# all.net
KiCad netlist of a schematic drawn in EAGLE
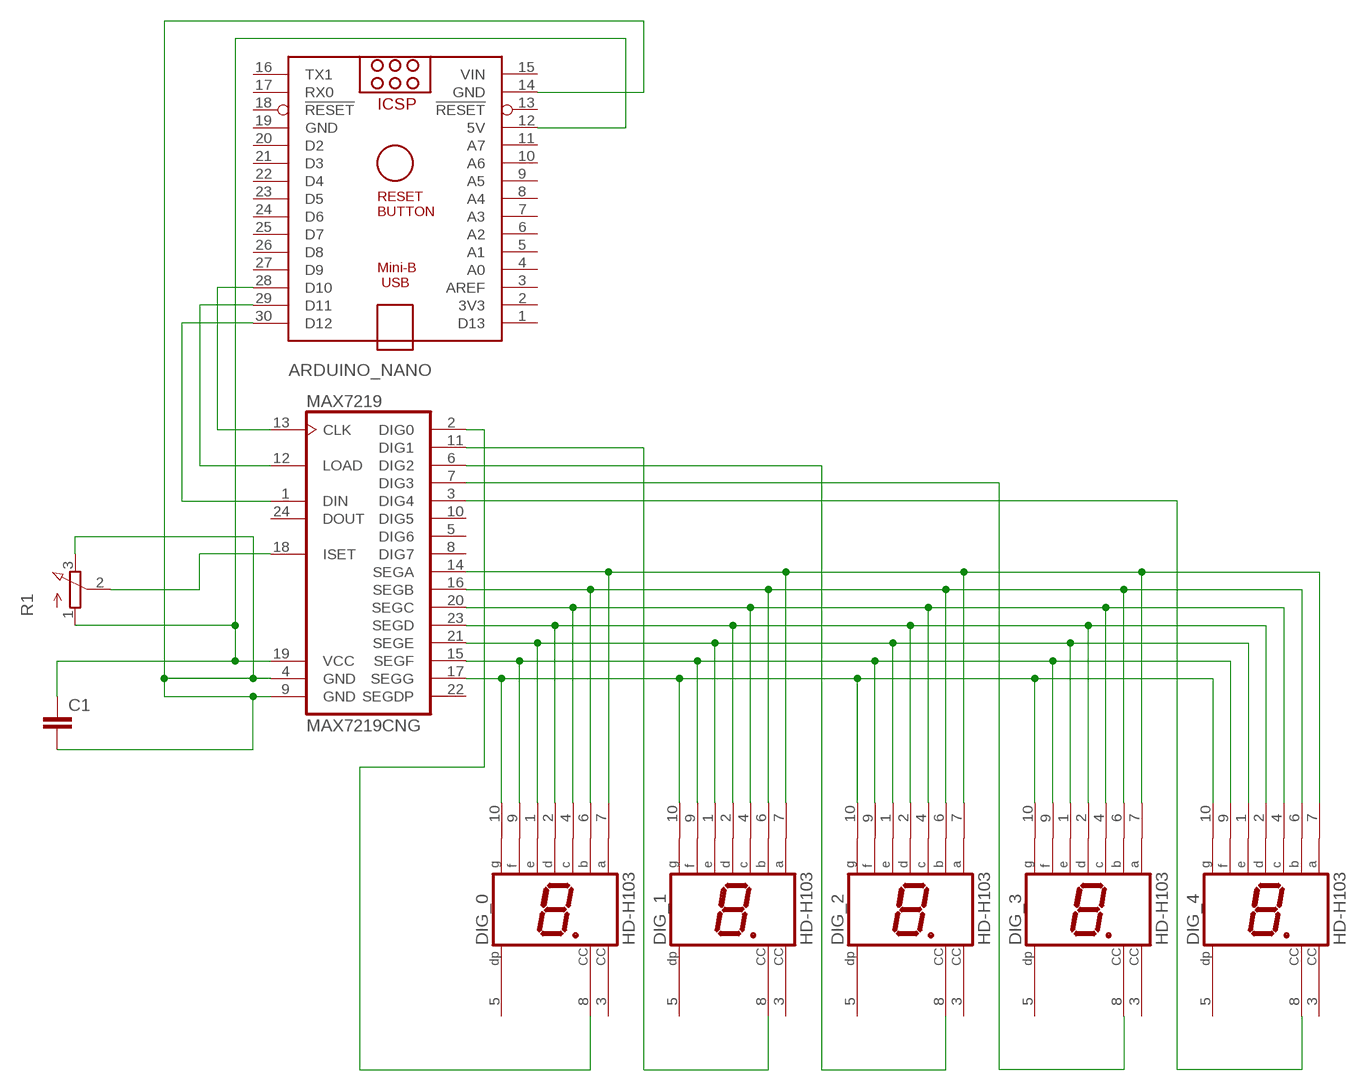
[diagram p0: schematic, sheet 1]

(export (version "E")
  (design (tool "Eeschema 10.0.6"))
  (components
    (comp (ref "ARDUINO_NANO")
      (value "ARDUINO_NANO")
      (footprint "eagle-import:ARDUINO_NANO")
      (libsource (lib "eagle-import") (part "ARDUINO_NANO"))
    )
    (comp (ref "C1")
      (value "C2,5-3")
      (footprint "eagle-import:C2.5-3")
      (libsource (lib "eagle-import") (part "C2,5-3"))
    )
    (comp (ref "DIG_0")
      (value "HD-H103")
      (footprint "eagle-import:HDSP-M")
      (libsource (lib "eagle-import") (part "HD-H103"))
    )
    (comp (ref "DIG_1")
      (value "HD-H103")
      (footprint "eagle-import:HDSP-M")
      (libsource (lib "eagle-import") (part "HD-H103"))
    )
    (comp (ref "DIG_2")
      (value "HD-H103")
      (footprint "eagle-import:HDSP-M")
      (libsource (lib "eagle-import") (part "HD-H103"))
    )
    (comp (ref "DIG_3")
      (value "HD-H103")
      (footprint "eagle-import:HDSP-M")
      (libsource (lib "eagle-import") (part "HD-H103"))
    )
    (comp (ref "DIG_4")
      (value "HD-H103")
      (footprint "eagle-import:HDSP-M")
      (libsource (lib "eagle-import") (part "HD-H103"))
    )
    (comp (ref "MAX7219")
      (value "MAX7219CNG")
      (footprint "eagle-import:DIL24-3")
      (fields (field (name "MF") "MAXIM"))
      (libsource (lib "eagle-import") (part "MAX7219CNG"))
    )
    (comp (ref "R1")
      (value "3RP/1610N")
      (footprint "eagle-import:3RP_1610N")
      (libsource (lib "eagle-import") (part "3RP/1610N"))
    )
  )
  (nets
    (net (code "1") (name "/GND") (class "Default")
      (node (ref "ARDUINO_NANO") (pin "19") (pinfunction "GND_19") (pintype "power_in"))
    )
    (net (code "2") (name "/VIN") (class "Default")
      (node (ref "ARDUINO_NANO") (pin "15") (pinfunction "VIN_15") (pintype "power_in"))
    )
    (net (code "3") (name "Net-(ARDUINO_NANO-5V)") (class "Default")
      (node (ref "ARDUINO_NANO") (pin "12") (pinfunction "5V_12") (pintype "power_in"))
      (node (ref "C1") (pin "1") (pinfunction "1_1") (pintype "passive"))
      (node (ref "MAX7219") (pin "19") (pinfunction "VCC_19") (pintype "power_in"))
      (node (ref "R1") (pin "1") (pinfunction "A_1") (pintype "passive"))
    )
    (net (code "4") (name "Net-(ARDUINO_NANO-D10)") (class "Default")
      (node (ref "ARDUINO_NANO") (pin "28") (pinfunction "D10_28") (pintype "bidirectional"))
      (node (ref "MAX7219") (pin "13") (pinfunction "CLK_13") (pintype "input"))
    )
    (net (code "5") (name "Net-(ARDUINO_NANO-D11)") (class "Default")
      (node (ref "ARDUINO_NANO") (pin "29") (pinfunction "D11_29") (pintype "bidirectional"))
      (node (ref "MAX7219") (pin "12") (pinfunction "LOAD_12") (pintype "input"))
    )
    (net (code "6") (name "Net-(ARDUINO_NANO-D12)") (class "Default")
      (node (ref "ARDUINO_NANO") (pin "30") (pinfunction "D12_30") (pintype "bidirectional"))
      (node (ref "MAX7219") (pin "1") (pinfunction "DIN_1") (pintype "input"))
    )
    (net (code "7") (name "Net-(DIG_0-A)") (class "Default")
      (node (ref "DIG_0") (pin "7") (pinfunction "A_7") (pintype "passive"))
      (node (ref "DIG_1") (pin "7") (pinfunction "A_7") (pintype "passive"))
      (node (ref "DIG_2") (pin "7") (pinfunction "A_7") (pintype "passive"))
      (node (ref "DIG_3") (pin "7") (pinfunction "A_7") (pintype "passive"))
      (node (ref "DIG_4") (pin "7") (pinfunction "A_7") (pintype "passive"))
      (node (ref "MAX7219") (pin "14") (pinfunction "SEGA_14") (pintype "output"))
    )
    (net (code "8") (name "Net-(DIG_0-B)") (class "Default")
      (node (ref "DIG_0") (pin "6") (pinfunction "B_6") (pintype "passive"))
      (node (ref "DIG_1") (pin "6") (pinfunction "B_6") (pintype "passive"))
      (node (ref "DIG_2") (pin "6") (pinfunction "B_6") (pintype "passive"))
      (node (ref "DIG_3") (pin "6") (pinfunction "B_6") (pintype "passive"))
      (node (ref "DIG_4") (pin "6") (pinfunction "B_6") (pintype "passive"))
      (node (ref "MAX7219") (pin "16") (pinfunction "SEGB_16") (pintype "output"))
    )
    (net (code "9") (name "Net-(DIG_0-C)") (class "Default")
      (node (ref "DIG_0") (pin "4") (pinfunction "C_4") (pintype "passive"))
      (node (ref "DIG_1") (pin "4") (pinfunction "C_4") (pintype "passive"))
      (node (ref "DIG_2") (pin "4") (pinfunction "C_4") (pintype "passive"))
      (node (ref "DIG_3") (pin "4") (pinfunction "C_4") (pintype "passive"))
      (node (ref "DIG_4") (pin "4") (pinfunction "C_4") (pintype "passive"))
      (node (ref "MAX7219") (pin "20") (pinfunction "SEGC_20") (pintype "output"))
    )
    (net (code "10") (name "Net-(DIG_0-D)") (class "Default")
      (node (ref "DIG_0") (pin "2") (pinfunction "D_2") (pintype "passive"))
      (node (ref "DIG_1") (pin "2") (pinfunction "D_2") (pintype "passive"))
      (node (ref "DIG_2") (pin "2") (pinfunction "D_2") (pintype "passive"))
      (node (ref "DIG_3") (pin "2") (pinfunction "D_2") (pintype "passive"))
      (node (ref "DIG_4") (pin "2") (pinfunction "D_2") (pintype "passive"))
      (node (ref "MAX7219") (pin "23") (pinfunction "SEGD_23") (pintype "output"))
    )
    (net (code "11") (name "Net-(DIG_0-E)") (class "Default")
      (node (ref "DIG_0") (pin "1") (pinfunction "E_1") (pintype "passive"))
      (node (ref "DIG_1") (pin "1") (pinfunction "E_1") (pintype "passive"))
      (node (ref "DIG_2") (pin "1") (pinfunction "E_1") (pintype "passive"))
      (node (ref "DIG_3") (pin "1") (pinfunction "E_1") (pintype "passive"))
      (node (ref "DIG_4") (pin "1") (pinfunction "E_1") (pintype "passive"))
      (node (ref "MAX7219") (pin "21") (pinfunction "SEGE_21") (pintype "output"))
    )
    (net (code "12") (name "Net-(DIG_0-F)") (class "Default")
      (node (ref "DIG_0") (pin "9") (pinfunction "F_9") (pintype "passive"))
      (node (ref "DIG_1") (pin "9") (pinfunction "F_9") (pintype "passive"))
      (node (ref "DIG_2") (pin "9") (pinfunction "F_9") (pintype "passive"))
      (node (ref "DIG_3") (pin "9") (pinfunction "F_9") (pintype "passive"))
      (node (ref "DIG_4") (pin "9") (pinfunction "F_9") (pintype "passive"))
      (node (ref "MAX7219") (pin "15") (pinfunction "SEGF_15") (pintype "output"))
    )
    (net (code "13") (name "Net-(DIG_0-G)") (class "Default")
      (node (ref "DIG_0") (pin "10") (pinfunction "G_10") (pintype "passive"))
      (node (ref "DIG_1") (pin "10") (pinfunction "G_10") (pintype "passive"))
      (node (ref "DIG_2") (pin "10") (pinfunction "G_10") (pintype "passive"))
      (node (ref "DIG_3") (pin "10") (pinfunction "G_10") (pintype "passive"))
      (node (ref "DIG_4") (pin "10") (pinfunction "G_10") (pintype "passive"))
      (node (ref "MAX7219") (pin "17") (pinfunction "SEGG_17") (pintype "output"))
    )
    (net (code "14") (name "Net-(MAX7219-DIG0)") (class "Default")
      (node (ref "DIG_0") (pin "8") (pinfunction "CC_8") (pintype "passive"))
      (node (ref "MAX7219") (pin "2") (pinfunction "DIG0_2") (pintype "output"))
    )
    (net (code "15") (name "Net-(MAX7219-DIG1)") (class "Default")
      (node (ref "DIG_1") (pin "8") (pinfunction "CC_8") (pintype "passive"))
      (node (ref "MAX7219") (pin "11") (pinfunction "DIG1_11") (pintype "output"))
    )
    (net (code "16") (name "Net-(MAX7219-DIG2)") (class "Default")
      (node (ref "DIG_2") (pin "8") (pinfunction "CC_8") (pintype "passive"))
      (node (ref "MAX7219") (pin "6") (pinfunction "DIG2_6") (pintype "output"))
    )
    (net (code "17") (name "Net-(MAX7219-DIG3)") (class "Default")
      (node (ref "DIG_3") (pin "8") (pinfunction "CC_8") (pintype "passive"))
      (node (ref "MAX7219") (pin "7") (pinfunction "DIG3_7") (pintype "output"))
    )
    (net (code "18") (name "Net-(MAX7219-DIG4)") (class "Default")
      (node (ref "DIG_4") (pin "8") (pinfunction "CC_8") (pintype "passive"))
      (node (ref "MAX7219") (pin "3") (pinfunction "DIG4_3") (pintype "output"))
    )
    (net (code "19") (name "Net-(MAX7219-ISET)") (class "Default")
      (node (ref "MAX7219") (pin "18") (pinfunction "ISET_18") (pintype "input"))
      (node (ref "R1") (pin "2") (pinfunction "S_2") (pintype "passive"))
    )
    (net (code "20") (name "Net-(R1-E)") (class "Default")
      (node (ref "ARDUINO_NANO") (pin "14") (pinfunction "GND_14") (pintype "power_in"))
      (node (ref "C1") (pin "2") (pinfunction "2_2") (pintype "passive"))
      (node (ref "MAX7219") (pin "4") (pinfunction "GND_4") (pintype "power_in"))
      (node (ref "MAX7219") (pin "9") (pinfunction "GND_9") (pintype "power_in"))
      (node (ref "R1") (pin "3") (pinfunction "E_3") (pintype "passive"))
    )
    (net (code "21") (name "unconnected-(ARDUINO_NANO-3V3-Pad2)") (class "Default")
      (node (ref "ARDUINO_NANO") (pin "2") (pinfunction "3V3_2") (pintype "output"))
    )
    (net (code "22") (name "unconnected-(ARDUINO_NANO-A0-Pad4)") (class "Default")
      (node (ref "ARDUINO_NANO") (pin "4") (pinfunction "A0_4") (pintype "bidirectional"))
    )
    (net (code "23") (name "unconnected-(ARDUINO_NANO-A1-Pad5)") (class "Default")
      (node (ref "ARDUINO_NANO") (pin "5") (pinfunction "A1_5") (pintype "bidirectional"))
    )
    (net (code "24") (name "unconnected-(ARDUINO_NANO-A2-Pad6)") (class "Default")
      (node (ref "ARDUINO_NANO") (pin "6") (pinfunction "A2_6") (pintype "bidirectional"))
    )
    (net (code "25") (name "unconnected-(ARDUINO_NANO-A3-Pad7)") (class "Default")
      (node (ref "ARDUINO_NANO") (pin "7") (pinfunction "A3_7") (pintype "bidirectional"))
    )
    (net (code "26") (name "unconnected-(ARDUINO_NANO-A4-Pad8)") (class "Default")
      (node (ref "ARDUINO_NANO") (pin "8") (pinfunction "A4_8") (pintype "bidirectional"))
    )
    (net (code "27") (name "unconnected-(ARDUINO_NANO-A5-Pad9)") (class "Default")
      (node (ref "ARDUINO_NANO") (pin "9") (pinfunction "A5_9") (pintype "bidirectional"))
    )
    (net (code "28") (name "unconnected-(ARDUINO_NANO-A6-Pad10)") (class "Default")
      (node (ref "ARDUINO_NANO") (pin "10") (pinfunction "A6_10") (pintype "bidirectional"))
    )
    (net (code "29") (name "unconnected-(ARDUINO_NANO-A7-Pad11)") (class "Default")
      (node (ref "ARDUINO_NANO") (pin "11") (pinfunction "A7_11") (pintype "bidirectional"))
    )
    (net (code "30") (name "unconnected-(ARDUINO_NANO-AREF-Pad3)") (class "Default")
      (node (ref "ARDUINO_NANO") (pin "3") (pinfunction "AREF_3") (pintype "input"))
    )
    (net (code "31") (name "unconnected-(ARDUINO_NANO-D2-Pad20)") (class "Default")
      (node (ref "ARDUINO_NANO") (pin "20") (pinfunction "D2_20") (pintype "bidirectional"))
    )
    (net (code "32") (name "unconnected-(ARDUINO_NANO-D3-Pad21)") (class "Default")
      (node (ref "ARDUINO_NANO") (pin "21") (pinfunction "D3_21") (pintype "bidirectional"))
    )
    (net (code "33") (name "unconnected-(ARDUINO_NANO-D4-Pad22)") (class "Default")
      (node (ref "ARDUINO_NANO") (pin "22") (pinfunction "D4_22") (pintype "bidirectional"))
    )
    (net (code "34") (name "unconnected-(ARDUINO_NANO-D5-Pad23)") (class "Default")
      (node (ref "ARDUINO_NANO") (pin "23") (pinfunction "D5_23") (pintype "bidirectional"))
    )
    (net (code "35") (name "unconnected-(ARDUINO_NANO-D6-Pad24)") (class "Default")
      (node (ref "ARDUINO_NANO") (pin "24") (pinfunction "D6_24") (pintype "bidirectional"))
    )
    (net (code "36") (name "unconnected-(ARDUINO_NANO-D7-Pad25)") (class "Default")
      (node (ref "ARDUINO_NANO") (pin "25") (pinfunction "D7_25") (pintype "bidirectional"))
    )
    (net (code "37") (name "unconnected-(ARDUINO_NANO-D8-Pad26)") (class "Default")
      (node (ref "ARDUINO_NANO") (pin "26") (pinfunction "D8_26") (pintype "bidirectional"))
    )
    (net (code "38") (name "unconnected-(ARDUINO_NANO-D9-Pad27)") (class "Default")
      (node (ref "ARDUINO_NANO") (pin "27") (pinfunction "D9_27") (pintype "bidirectional"))
    )
    (net (code "39") (name "unconnected-(ARDUINO_NANO-D13-Pad1)") (class "Default")
      (node (ref "ARDUINO_NANO") (pin "1") (pinfunction "D13_1") (pintype "bidirectional"))
    )
    (net (code "40") (name "unconnected-(ARDUINO_NANO-RX0-Pad17)") (class "Default")
      (node (ref "ARDUINO_NANO") (pin "17") (pinfunction "RX0_17") (pintype "bidirectional"))
    )
    (net (code "41") (name "unconnected-(ARDUINO_NANO-TX1-Pad16)") (class "Default")
      (node (ref "ARDUINO_NANO") (pin "16") (pinfunction "TX1_16") (pintype "bidirectional"))
    )
    (net (code "42") (name "unconnected-(ARDUINO_NANO-~{RESET}-Pad13)") (class "Default")
      (node (ref "ARDUINO_NANO") (pin "13") (pinfunction "~{RESET}_13") (pintype "input"))
    )
    (net (code "43") (name "unconnected-(ARDUINO_NANO-~{RESET}-Pad18)") (class "Default")
      (node (ref "ARDUINO_NANO") (pin "18") (pinfunction "~{RESET}_18") (pintype "input"))
    )
    (net (code "44") (name "unconnected-(DIG_0-CC-Pad3)") (class "Default")
      (node (ref "DIG_0") (pin "3") (pinfunction "CC_3") (pintype "passive"))
    )
    (net (code "45") (name "unconnected-(DIG_0-DP-Pad5)") (class "Default")
      (node (ref "DIG_0") (pin "5") (pinfunction "DP_5") (pintype "passive"))
    )
    (net (code "46") (name "unconnected-(DIG_1-CC-Pad3)") (class "Default")
      (node (ref "DIG_1") (pin "3") (pinfunction "CC_3") (pintype "passive"))
    )
    (net (code "47") (name "unconnected-(DIG_1-DP-Pad5)") (class "Default")
      (node (ref "DIG_1") (pin "5") (pinfunction "DP_5") (pintype "passive"))
    )
    (net (code "48") (name "unconnected-(DIG_2-CC-Pad3)") (class "Default")
      (node (ref "DIG_2") (pin "3") (pinfunction "CC_3") (pintype "passive"))
    )
    (net (code "49") (name "unconnected-(DIG_2-DP-Pad5)") (class "Default")
      (node (ref "DIG_2") (pin "5") (pinfunction "DP_5") (pintype "passive"))
    )
    (net (code "50") (name "unconnected-(DIG_3-CC-Pad3)") (class "Default")
      (node (ref "DIG_3") (pin "3") (pinfunction "CC_3") (pintype "passive"))
    )
    (net (code "51") (name "unconnected-(DIG_3-DP-Pad5)") (class "Default")
      (node (ref "DIG_3") (pin "5") (pinfunction "DP_5") (pintype "passive"))
    )
    (net (code "52") (name "unconnected-(DIG_4-CC-Pad3)") (class "Default")
      (node (ref "DIG_4") (pin "3") (pinfunction "CC_3") (pintype "passive"))
    )
    (net (code "53") (name "unconnected-(DIG_4-DP-Pad5)") (class "Default")
      (node (ref "DIG_4") (pin "5") (pinfunction "DP_5") (pintype "passive"))
    )
    (net (code "54") (name "unconnected-(MAX7219-DIG5-Pad10)") (class "Default")
      (node (ref "MAX7219") (pin "10") (pinfunction "DIG5_10") (pintype "output"))
    )
    (net (code "55") (name "unconnected-(MAX7219-DIG6-Pad5)") (class "Default")
      (node (ref "MAX7219") (pin "5") (pinfunction "DIG6_5") (pintype "output"))
    )
    (net (code "56") (name "unconnected-(MAX7219-DIG7-Pad8)") (class "Default")
      (node (ref "MAX7219") (pin "8") (pinfunction "DIG7_8") (pintype "output"))
    )
    (net (code "57") (name "unconnected-(MAX7219-DOUT-Pad24)") (class "Default")
      (node (ref "MAX7219") (pin "24") (pinfunction "DOUT_24") (pintype "output"))
    )
    (net (code "58") (name "unconnected-(MAX7219-SEGDP-Pad22)") (class "Default")
      (node (ref "MAX7219") (pin "22") (pinfunction "SEGDP_22") (pintype "output"))
    )
  )
)
